# DS130-1_02_G-M.net
KiCad netlist of a schematic drawn in Altium Designer
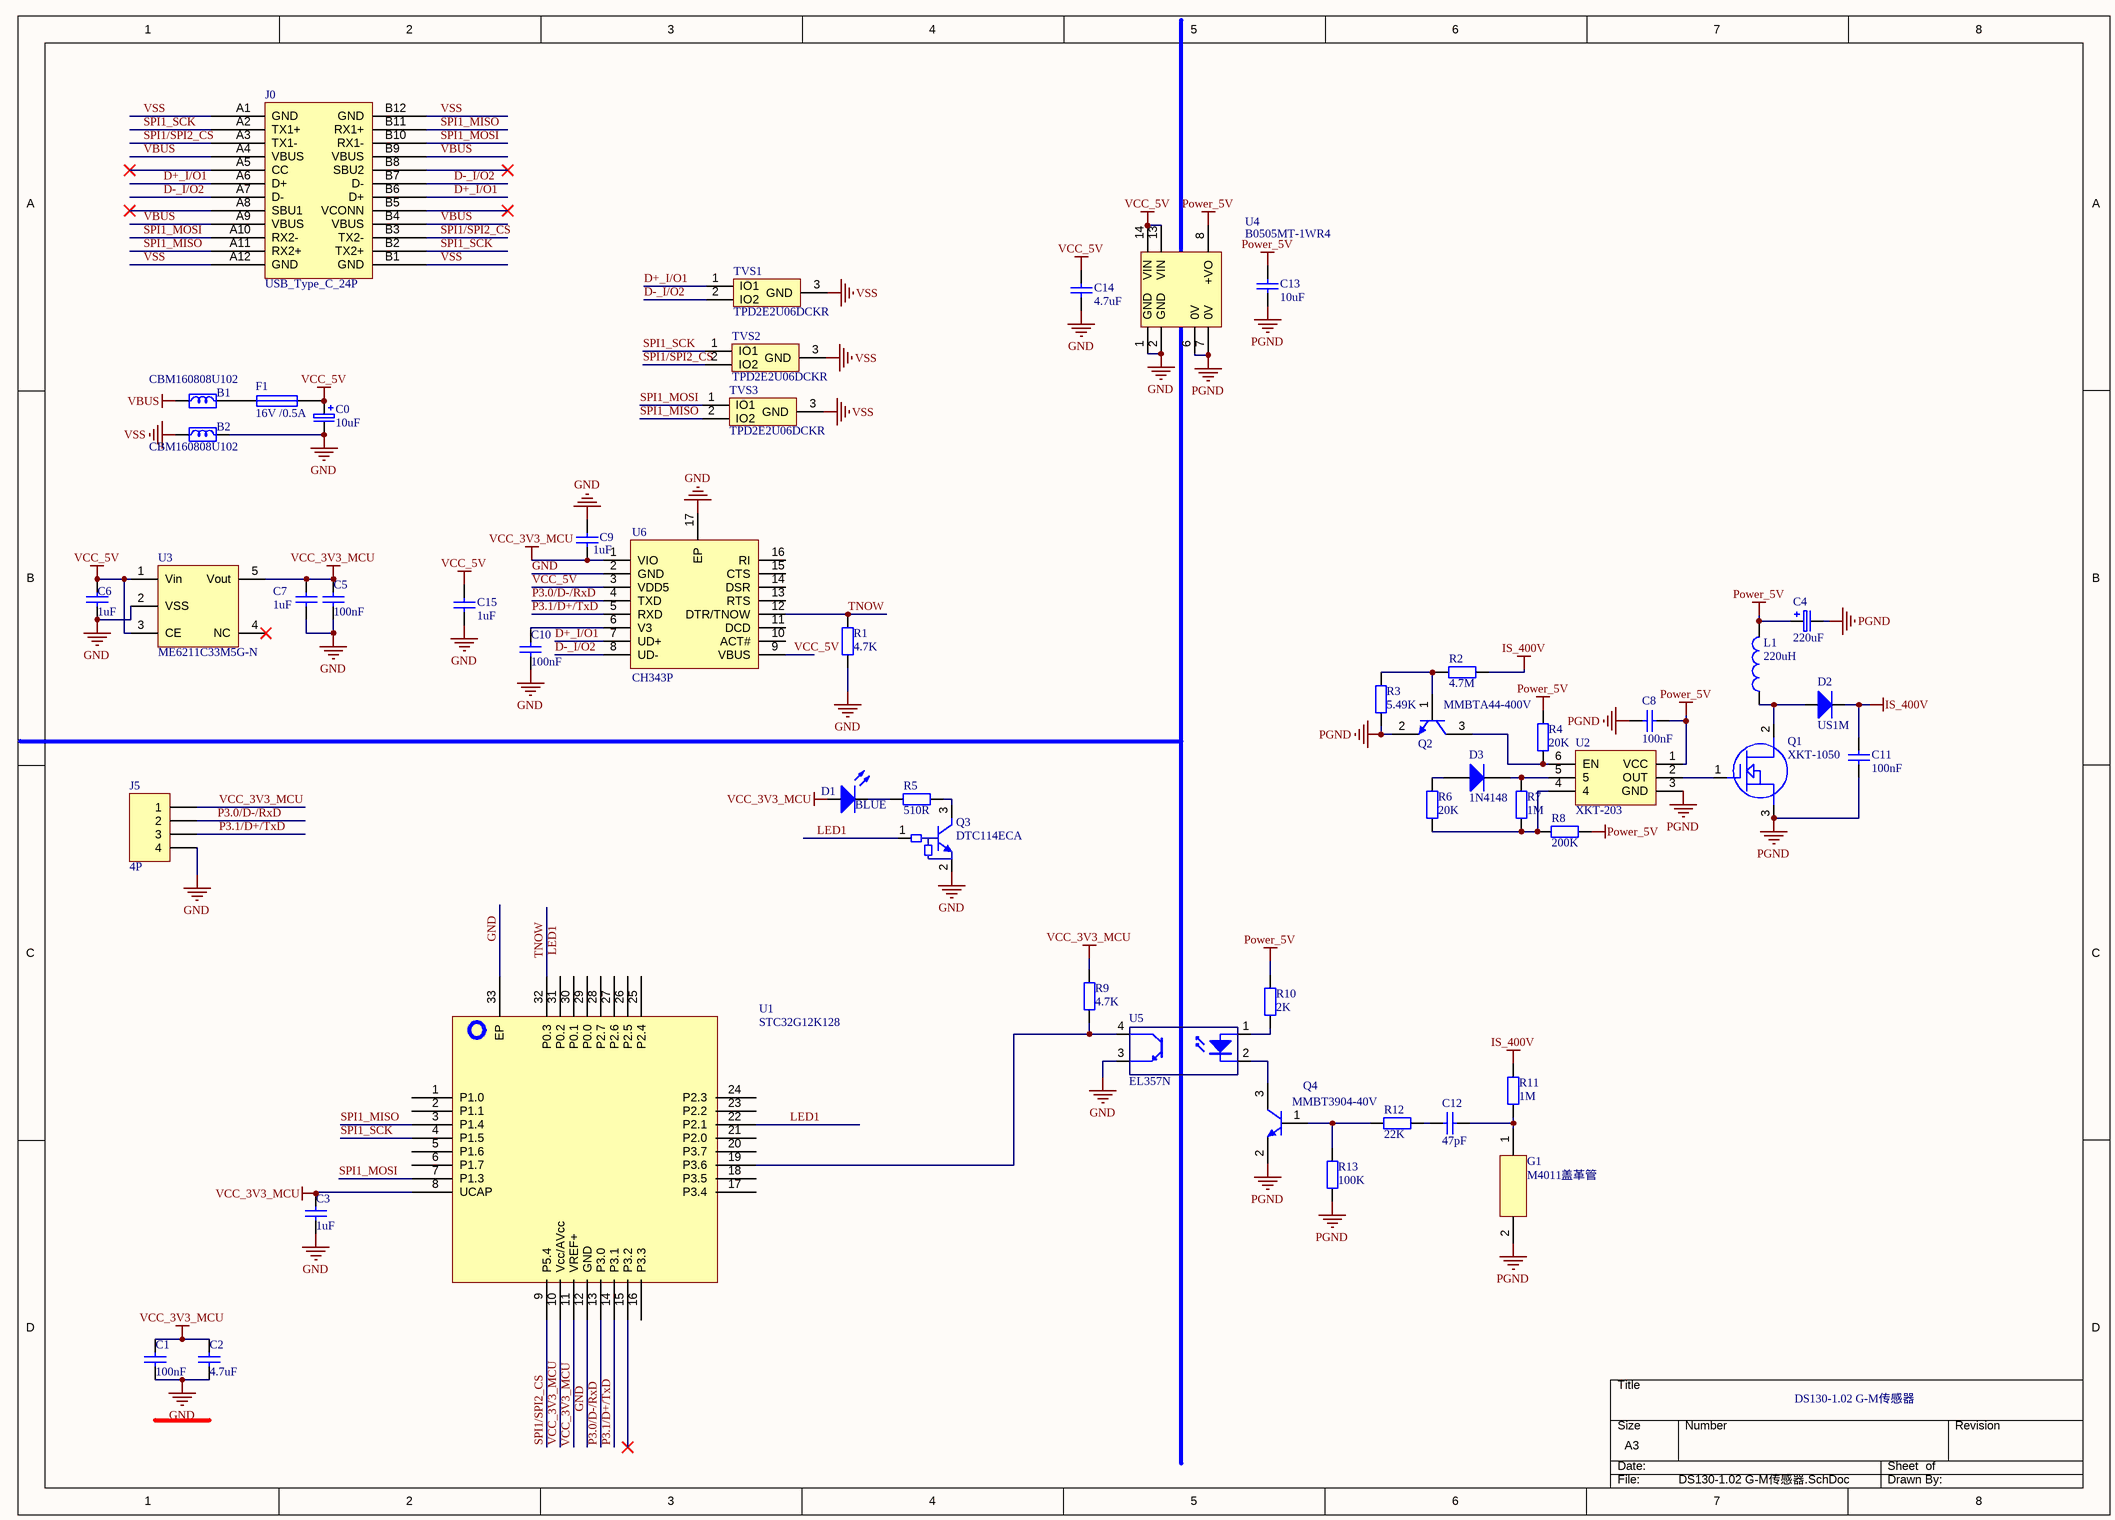
[diagram p0: DS130-1.02 G-M传感器.SchDoc]

(export (version "E")
  (design (tool "Eeschema 10.0.6"))
  (components
    (comp (ref "B1")
      (value "CBM160808U102")
      (footprint "0603Bead")
      (description "贴片磁珠")
      (libsource (lib "AD_SCH") (part "Chip Ferrite Bead 0606"))
    )
    (comp (ref "B2")
      (value "CBM160808U102")
      (footprint "0603Bead")
      (description "贴片磁珠")
      (libsource (lib "AD_SCH") (part "Chip Ferrite Bead 0606"))
    )
    (comp (ref "C0")
      (value "10uF")
      (footprint "AVX_3216-18(1206)_SMD")
      (description "钽电容")
      (fields (field (name "Comment") "AVX_10uF/16V ±10％(C106)"))
      (libsource (lib "AD_SCH") (part "AVX_10uF/16V ±10％(C106)"))
    )
    (comp (ref "C1")
      (value "100nF")
      (footprint "0603CAP")
      (description "贴片电容")
      (fields (field (name "Comment") "SMDCAP00013"))
      (libsource (lib "AD_SCH") (part "MLCC 100nF 50V ±10％ 0603"))
    )
    (comp (ref "C2")
      (value "4.7uF")
      (footprint "0603CAP")
      (description "贴片电容")
      (fields (field (name "Comment") "SMDCAP00012"))
      (libsource (lib "AD_SCH") (part "MLCC 4.7uF 50V ±10％ 0603"))
    )
    (comp (ref "C3")
      (value "1uF")
      (footprint "0603CAP")
      (description "贴片电容")
      (fields (field (name "Comment") "SMDCAP00015"))
      (libsource (lib "AD_SCH") (part "MLCC 1uF 50V ±10％ 0603"))
    )
    (comp (ref "C4")
      (value "220uF")
      (footprint "AVX_7343-31(2917)_SMD")
      (description "钽电容")
      (fields (field (name "Comment") "AVX_220uF/16V ±10％(C227)"))
      (libsource (lib "AD_SCH") (part "AVX_220uF/16V ±10％(C227)"))
    )
    (comp (ref "C5")
      (value "100nF")
      (footprint "0603CAP")
      (description "贴片电容")
      (fields (field (name "Comment") "SMDCAP00013"))
      (libsource (lib "AD_SCH") (part "MLCC 100nF 50V ±10％ 0603"))
    )
    (comp (ref "C6")
      (value "1uF")
      (footprint "0603CAP")
      (description "贴片电容")
      (fields (field (name "Comment") "SMDCAP00015"))
      (libsource (lib "AD_SCH") (part "MLCC 1uF 50V ±10％ 0603"))
    )
    (comp (ref "C7")
      (value "1uF")
      (footprint "0603CAP")
      (description "贴片电容")
      (fields (field (name "Comment") "SMDCAP00015"))
      (libsource (lib "AD_SCH") (part "MLCC 1uF 50V ±10％ 0603"))
    )
    (comp (ref "C8")
      (value "100nF")
      (footprint "0603CAP")
      (description "贴片电容")
      (fields (field (name "Comment") "SMDCAP00013"))
      (libsource (lib "AD_SCH") (part "MLCC 100nF 50V ±10％ 0603"))
    )
    (comp (ref "C9")
      (value "1uF")
      (footprint "0603CAP")
      (description "贴片电容")
      (fields (field (name "Comment") "SMDCAP00015"))
      (libsource (lib "AD_SCH") (part "MLCC 1uF 50V ±10％ 0603"))
    )
    (comp (ref "C10")
      (value "100nF")
      (footprint "0603CAP")
      (description "贴片电容")
      (fields (field (name "Comment") "SMDCAP00013"))
      (libsource (lib "AD_SCH") (part "MLCC 100nF 50V ±10％ 0603"))
    )
    (comp (ref "C11")
      (value "100nF")
      (footprint "DIP_CL_10.16mm")
      (description "插件涤纶电容")
      (fields (field (name "Comment") "DIPCAP03003"))
      (libsource (lib "AD_SCH") (part "CBB22 100nF 630VDC ±5％ DIP2"))
    )
    (comp (ref "C12")
      (value "47pF")
      (footprint "1206CAP")
      (description "贴片电容")
      (fields (field (name "Comment") "MLCC 47pF 1kV ±5％ 1206"))
      (libsource (lib "AD_SCH") (part "MLCC 47pF 1kV ±5％ 1206"))
    )
    (comp (ref "C13")
      (value "10uF")
      (footprint "0603CAP")
      (description "贴片电容")
      (fields (field (name "Comment") "SMDCAP00016"))
      (libsource (lib "AD_SCH") (part "MLCC 10uF 50V ±10％ 0603"))
    )
    (comp (ref "C14")
      (value "4.7uF")
      (footprint "0603CAP")
      (description "贴片电容")
      (fields (field (name "Comment") "SMDCAP00012"))
      (libsource (lib "AD_SCH") (part "MLCC 4.7uF 50V ±10％ 0603"))
    )
    (comp (ref "C15")
      (value "1uF")
      (footprint "0603CAP")
      (description "贴片电容")
      (fields (field (name "Comment") "SMDCAP00015"))
      (libsource (lib "AD_SCH") (part "MLCC 1uF 50V ±10％ 0603"))
    )
    (comp (ref "D1")
      (value "BLUE")
      (footprint "LED_0805")
      (description "贴片LED")
      (fields (field (name "Comment") "SMDLED00010"))
      (libsource (lib "AD_SCH") (part "Chip 蓝色LED 0805"))
    )
    (comp (ref "D2")
      (value "US1M")
      (footprint "SMA/DO-214AC")
      (description "快恢复/高效率二极管")
      (fields (field (name "Comment") "US1M-DO-214AC"))
      (libsource (lib "AD_SCH") (part "US1M-DO-214AC"))
    )
    (comp (ref "D3")
      (value "1N4148")
      (footprint "SOD-123")
      (description "贴片开关二极管 T4")
      (fields (field (name "Comment") "DIPDIODE02001"))
      (libsource (lib "AD_SCH") (part "1N4148W"))
    )
    (comp (ref "F1")
      (value "16V /0.5A")
      (footprint "1206FUSE")
      (description "贴片自恢复保险丝 16V /0.5A")
      (fields (field (name "Comment") "SMD1206-050C-16V"))
      (libsource (lib "AD_SCH") (part "SMD1206-050C-16V"))
    )
    (comp (ref "G1") (value "M4011盖革管") (footprint "M4011-90") (libsource (lib "AD_SCH") (part "M4011盖革管")))
    (comp (ref "J0")
      (value "USB_Type_C_24P")
      (footprint "USB_TYPE_C_24P_Receptacle")
      (libsource (lib "AD_SCH") (part "USB_Type_C_24P"))
    )
    (comp (ref "J5")
      (value "4P")
      (footprint "H4")
      (description "单排直针")
      (fields (field (name "Comment") "DIP4单排直针  间距2mm 针长11mm 铜"))
      (libsource (lib "AD_SCH") (part "DIP4单排直针  间距2mm 针长11mm 铜"))
    )
    (comp (ref "L1")
      (value "220uH")
      (footprint "IND-SMD_L8.0-W8.0")
      (fields (field (name "Comment") "SMD_220uH 8.0*8.0"))
      (libsource (lib "AD_SCH") (part "SMD_220uH 8.0*8.0"))
    )
    (comp (ref "Q1")
      (value "XKT-1050")
      (footprint "TO-252")
      (description "NMOS")
      (libsource (lib "AD_SCH") (part "XKT-1050"))
    )
    (comp (ref "Q2")
      (value "MMBTA44-400V")
      (footprint "SOT23")
      (description "BJT")
      (fields (field (name "Comment") "MMBTA44"))
      (libsource (lib "AD_SCH") (part "MMBTA44"))
    )
    (comp (ref "Q3")
      (value "DTC114ECA")
      (footprint "SOT23")
      (description "数字晶体管")
      (fields (field (name "Comment") "SMDIC000037"))
      (libsource (lib "AD_SCH") (part "DTC114ECA SOT-23 长电"))
    )
    (comp (ref "Q4")
      (value "MMBT3904-40V")
      (footprint "SOT23")
      (description "BJT")
      (fields (field (name "Comment") "MMBT3904"))
      (libsource (lib "AD_SCH") (part "MMBT3904"))
    )
    (comp (ref "R1")
      (value "4.7K")
      (footprint "0603RES")
      (description "贴片电阻")
      (fields (field (name "Comment") "Chip 4.7K 1/16W ±1％ 0603"))
      (libsource (lib "AD_SCH") (part "Chip 4.7K 1/16W ±1％ 0603"))
    )
    (comp (ref "R2")
      (value "4.7M")
      (footprint "1206RES")
      (description "贴片电阻")
      (fields (field (name "Comment") "Chip 4.7M 1/4W ±1％ 1206 500V"))
      (libsource (lib "AD_SCH") (part "Chip 4.7M 1/4W ±1％ 1206 500V"))
    )
    (comp (ref "R3")
      (value "5.49K")
      (footprint "0603RES")
      (description "贴片电阻")
      (fields (field (name "Comment") "Chip 5.49K 1/10W ±1％ 0603"))
      (libsource (lib "AD_SCH") (part "Chip 5.49K 1/10W ±1％ 0603"))
    )
    (comp (ref "R4")
      (value "20K")
      (footprint "0603RES")
      (description "贴片电阻")
      (fields (field (name "Comment") "SMDRES00058"))
      (libsource (lib "AD_SCH") (part "Chip 20K 1/16W ±1％ 0603"))
    )
    (comp (ref "R5")
      (value "510R")
      (footprint "0603RES")
      (description "贴片电阻")
      (fields (field (name "Comment") "SMDRES00030"))
      (libsource (lib "AD_SCH") (part "Chip 510R 1/16W ±1％ 0603"))
    )
    (comp (ref "R6")
      (value "20K")
      (footprint "0603RES")
      (description "贴片电阻")
      (fields (field (name "Comment") "SMDRES00058"))
      (libsource (lib "AD_SCH") (part "Chip 20K 1/16W ±1％ 0603"))
    )
    (comp (ref "R7")
      (value "1M")
      (footprint "0603RES")
      (description "贴片电阻")
      (fields (field (name "Comment") "SMDRES00085"))
      (libsource (lib "AD_SCH") (part "Chip 1M 1/16W ±1％ 0603"))
    )
    (comp (ref "R8")
      (value "200K")
      (footprint "0603RES")
      (description "贴片电阻")
      (fields (field (name "Comment") "SMDRES00075"))
      (libsource (lib "AD_SCH") (part "Chip 200K 1/16W ±1％ 0603"))
    )
    (comp (ref "R9")
      (value "4.7K")
      (footprint "0603RES")
      (description "贴片电阻")
      (fields (field (name "Comment") "Chip 4.7K 1/16W ±1％ 0603"))
      (libsource (lib "AD_SCH") (part "Chip 4.7K 1/16W ±1％ 0603"))
    )
    (comp (ref "R10")
      (value "2K")
      (footprint "0603RES")
      (description "贴片电阻")
      (fields (field (name "Comment") "SMDRES00042"))
      (libsource (lib "AD_SCH") (part "Chip 2K 1/16W ±1％ 0603"))
    )
    (comp (ref "R11")
      (value "1M")
      (footprint "0805RES")
      (description "贴片电阻")
      (fields (field (name "Comment") "Chip 1M 1/10W ±1％ 0805 400V"))
      (libsource (lib "AD_SCH") (part "Chip 1M 1/10W ±1％ 0805 400V"))
    )
    (comp (ref "R12")
      (value "22K")
      (footprint "0603RES")
      (description "贴片电阻")
      (fields (field (name "Comment") "SMDRES00108"))
      (libsource (lib "AD_SCH") (part "Chip 22K 1/16W ±1％ 0603"))
    )
    (comp (ref "R13")
      (value "100K")
      (footprint "0603RES")
      (description "贴片电阻")
      (fields (field (name "Comment") "SMDRES00071"))
      (libsource (lib "AD_SCH") (part "Chip 100K 1/16W ±1％ 0603"))
    )
    (comp (ref "TVS1")
      (value "TPD2E2U06DCKR")
      (footprint "SC-70-3_L2.0-W1.3-P0.65-LS2.1-BL")
      (libsource (lib "AD_SCH") (part "TPD2E2U06DCKR"))
    )
    (comp (ref "TVS2")
      (value "TPD2E2U06DCKR")
      (footprint "SC-70-3_L2.0-W1.3-P0.65-LS2.1-BL")
      (libsource (lib "AD_SCH") (part "TPD2E2U06DCKR"))
    )
    (comp (ref "TVS3")
      (value "TPD2E2U06DCKR")
      (footprint "SC-70-3_L2.0-W1.3-P0.65-LS2.1-BL")
      (libsource (lib "AD_SCH") (part "TPD2E2U06DCKR"))
    )
    (comp (ref "U1")
      (value "STC32G12K128")
      (footprint "QFN-32-L4.0-W4.0")
      (description "单片机芯片")
      (fields (field (name "Comment") "STC32G12K128_35I QFN32"))
      (libsource (lib "AD_SCH") (part "STC32G12K128_35I QFN32"))
    )
    (comp (ref "U2") (value "XKT-203") (footprint "SOT23-6") (libsource (lib "AD_SCH") (part "XKT-203")))
    (comp (ref "U3")
      (value "ME6211C33M5G-N")
      (footprint "SOT23-5")
      (description "稳压芯片")
      (libsource (lib "AD_SCH") (part "ME6211C33M5G-N"))
    )
    (comp (ref "U4")
      (value "B0505MT-1WR4")
      (footprint "DFN-14_7P_L9.0-W7.0-P1.27-BL_B0505MT-1WR4")
      (libsource (lib "AD_SCH") (part "B0505MT-1WR4"))
    )
    (comp (ref "U5")
      (value "EL357N")
      (footprint "SO-4")
      (description "光耦")
      (libsource (lib "AD_SCH") (part "EL357N"))
    )
    (comp (ref "U6") (value "CH343P") (footprint "QFN-16_L3_W3") (libsource (lib "AD_SCH") (part "CH343P")))
  )
  (nets
    (net (code "1") (name "/D+_I{slash}O1") (class "Default")
      (node (ref "J0") (pin "A6") (pinfunction "D+_A6") (pintype "passive"))
      (node (ref "J0") (pin "B6") (pinfunction "D+_B6") (pintype "passive"))
      (node (ref "TVS1") (pin "1") (pinfunction "IO1_1") (pintype "passive"))
      (node (ref "U6") (pin "7") (pinfunction "UD+_7") (pintype "passive"))
    )
    (net (code "2") (name "/D-_I{slash}O2") (class "Default")
      (node (ref "J0") (pin "A7") (pinfunction "D-_A7") (pintype "passive"))
      (node (ref "J0") (pin "B7") (pinfunction "D-_B7") (pintype "passive"))
      (node (ref "TVS1") (pin "2") (pinfunction "IO2_2") (pintype "passive"))
      (node (ref "U6") (pin "8") (pinfunction "UD-_8") (pintype "passive"))
    )
    (net (code "3") (name "/LED1") (class "Default")
      (node (ref "Q3") (pin "1") (pinfunction "IN_1") (pintype "passive"))
      (node (ref "U1") (pin "22") (pinfunction "P2.1_22") (pintype "passive"))
    )
    (net (code "4") (name "/P3.0{slash}D-{slash}RxD") (class "Default")
      (node (ref "J5") (pin "2") (pinfunction "2_2") (pintype "passive"))
      (node (ref "U1") (pin "13") (pinfunction "P3.0_13") (pintype "passive"))
      (node (ref "U6") (pin "4") (pinfunction "TXD_4") (pintype "passive"))
    )
    (net (code "5") (name "/P3.1{slash}D+{slash}TxD") (class "Default")
      (node (ref "J5") (pin "3") (pinfunction "3_3") (pintype "passive"))
      (node (ref "U1") (pin "14") (pinfunction "P3.1_14") (pintype "passive"))
      (node (ref "U6") (pin "5") (pinfunction "RXD_5") (pintype "passive"))
    )
    (net (code "6") (name "/SPI1_MISO") (class "Default")
      (node (ref "J0") (pin "A11") (pinfunction "RX2+_A11") (pintype "passive"))
      (node (ref "J0") (pin "B11") (pinfunction "RX1+_B11") (pintype "passive"))
      (node (ref "TVS3") (pin "2") (pinfunction "IO2_2") (pintype "passive"))
      (node (ref "U1") (pin "3") (pinfunction "P1.4_3") (pintype "passive"))
    )
    (net (code "7") (name "/SPI1_MOSI") (class "Default")
      (node (ref "J0") (pin "A10") (pinfunction "RX2-_A10") (pintype "passive"))
      (node (ref "J0") (pin "B10") (pinfunction "RX1-_B10") (pintype "passive"))
      (node (ref "TVS3") (pin "1") (pinfunction "IO1_1") (pintype "passive"))
      (node (ref "U1") (pin "7") (pinfunction "P1.3_7") (pintype "passive"))
    )
    (net (code "8") (name "/SPI1_SCK") (class "Default")
      (node (ref "J0") (pin "A2") (pinfunction "TX1+_A2") (pintype "passive"))
      (node (ref "J0") (pin "B2") (pinfunction "TX2+_B2") (pintype "passive"))
      (node (ref "TVS2") (pin "1") (pinfunction "IO1_1") (pintype "passive"))
      (node (ref "U1") (pin "4") (pinfunction "P1.5_4") (pintype "passive"))
    )
    (net (code "9") (name "/SPI1{slash}SPI2_CS") (class "Default")
      (node (ref "J0") (pin "A3") (pinfunction "TX1-_A3") (pintype "passive"))
      (node (ref "J0") (pin "B3") (pinfunction "TX2-_B3") (pintype "passive"))
      (node (ref "TVS2") (pin "2") (pinfunction "IO2_2") (pintype "passive"))
      (node (ref "U1") (pin "9") (pinfunction "P5.4_9") (pintype "passive"))
    )
    (net (code "10") (name "/TNOW") (class "Default")
      (node (ref "R1") (pin "2") (pinfunction "2_2") (pintype "passive"))
      (node (ref "U1") (pin "32") (pinfunction "P0.3_32") (pintype "passive"))
      (node (ref "U6") (pin "12") (pinfunction "DTR/TNOW_12") (pintype "passive"))
    )
    (net (code "11") (name "GND") (class "Default")
      (node (ref "B2") (pin "2") (pinfunction "2_2") (pintype "passive"))
      (node (ref "C0") (pin "2") (pinfunction "2_2") (pintype "passive"))
      (node (ref "C1") (pin "1") (pinfunction "1_1") (pintype "passive"))
      (node (ref "C10") (pin "1") (pinfunction "1_1") (pintype "passive"))
      (node (ref "C14") (pin "1") (pinfunction "1_1") (pintype "passive"))
      (node (ref "C15") (pin "1") (pinfunction "1_1") (pintype "passive"))
      (node (ref "C2") (pin "1") (pinfunction "1_1") (pintype "passive"))
      (node (ref "C3") (pin "1") (pinfunction "1_1") (pintype "passive"))
      (node (ref "C5") (pin "1") (pinfunction "1_1") (pintype "passive"))
      (node (ref "C6") (pin "1") (pinfunction "1_1") (pintype "passive"))
      (node (ref "C7") (pin "1") (pinfunction "1_1") (pintype "passive"))
      (node (ref "C9") (pin "2") (pinfunction "2_2") (pintype "passive"))
      (node (ref "J5") (pin "4") (pinfunction "4_4") (pintype "passive"))
      (node (ref "Q3") (pin "2") (pinfunction "GND_2") (pintype "passive"))
      (node (ref "R1") (pin "1") (pinfunction "1_1") (pintype "passive"))
      (node (ref "U1") (pin "12") (pinfunction "GND_12") (pintype "passive"))
      (node (ref "U1") (pin "33") (pinfunction "EP_33") (pintype "passive"))
      (node (ref "U3") (pin "2") (pinfunction "VSS_2") (pintype "passive"))
      (node (ref "U4") (pin "1") (pinfunction "GND_1") (pintype "passive"))
      (node (ref "U4") (pin "2") (pinfunction "GND_2") (pintype "passive"))
      (node (ref "U5") (pin "3") (pinfunction "E_3") (pintype "passive"))
      (node (ref "U6") (pin "17") (pinfunction "EP_17") (pintype "passive"))
      (node (ref "U6") (pin "2") (pinfunction "GND_2") (pintype "passive"))
    )
    (net (code "12") (name "IS_400V") (class "Default")
      (node (ref "C11") (pin "1") (pinfunction "1_1") (pintype "passive"))
      (node (ref "D2") (pin "2") (pinfunction "K_2") (pintype "passive"))
      (node (ref "R11") (pin "2") (pinfunction "2_2") (pintype "passive"))
      (node (ref "R2") (pin "2") (pinfunction "2_2") (pintype "passive"))
    )
    (net (code "13") (name "Net-(B1-Pad2)") (class "Default")
      (node (ref "B1") (pin "2") (pinfunction "2_2") (pintype "passive"))
      (node (ref "F1") (pin "1") (pinfunction "1_1") (pintype "passive"))
    )
    (net (code "14") (name "Net-(C12-Pad1)") (class "Default")
      (node (ref "C12") (pin "1") (pinfunction "1_1") (pintype "passive"))
      (node (ref "G1") (pin "1") (pinfunction "1_1") (pintype "passive"))
      (node (ref "R11") (pin "1") (pinfunction "1_1") (pintype "passive"))
    )
    (net (code "15") (name "Net-(C12-Pad2)") (class "Default")
      (node (ref "C12") (pin "2") (pinfunction "2_2") (pintype "passive"))
      (node (ref "R12") (pin "1") (pinfunction "1_1") (pintype "passive"))
    )
    (net (code "16") (name "Net-(D1-K)") (class "Default")
      (node (ref "D1") (pin "2") (pinfunction "K_2") (pintype "passive"))
      (node (ref "R5") (pin "1") (pinfunction "1_1") (pintype "passive"))
    )
    (net (code "17") (name "Net-(D2-A)") (class "Default")
      (node (ref "D2") (pin "1") (pinfunction "A_1") (pintype "passive"))
      (node (ref "L1") (pin "1") (pinfunction "1_1") (pintype "passive"))
      (node (ref "Q1") (pin "2") (pinfunction "D_2") (pintype "passive"))
    )
    (net (code "18") (name "Net-(D3-A)") (class "Default")
      (node (ref "D3") (pin "1") (pinfunction "A_1") (pintype "passive"))
      (node (ref "R6") (pin "2") (pinfunction "2_2") (pintype "passive"))
    )
    (net (code "19") (name "Net-(D3-K)") (class "Default")
      (node (ref "D3") (pin "2") (pinfunction "K_2") (pintype "passive"))
      (node (ref "R7") (pin "2") (pinfunction "2_2") (pintype "passive"))
      (node (ref "U2") (pin "5") (pinfunction "5_5") (pintype "passive"))
    )
    (net (code "20") (name "Net-(Q1-G)") (class "Default")
      (node (ref "Q1") (pin "1") (pinfunction "G_1") (pintype "passive"))
      (node (ref "U2") (pin "2") (pinfunction "OUT_2") (pintype "passive"))
    )
    (net (code "21") (name "Net-(Q2-B)") (class "Default")
      (node (ref "Q2") (pin "1") (pinfunction "B_1") (pintype "passive"))
      (node (ref "R2") (pin "1") (pinfunction "1_1") (pintype "passive"))
      (node (ref "R3") (pin "2") (pinfunction "2_2") (pintype "passive"))
    )
    (net (code "22") (name "Net-(Q2-C)") (class "Default")
      (node (ref "Q2") (pin "3") (pinfunction "C_3") (pintype "passive"))
      (node (ref "R4") (pin "1") (pinfunction "1_1") (pintype "passive"))
      (node (ref "U2") (pin "6") (pinfunction "EN_6") (pintype "passive"))
    )
    (net (code "23") (name "Net-(Q3-OUT)") (class "Default")
      (node (ref "Q3") (pin "3") (pinfunction "OUT_3") (pintype "passive"))
      (node (ref "R5") (pin "2") (pinfunction "2_2") (pintype "passive"))
    )
    (net (code "24") (name "Net-(Q4-B)") (class "Default")
      (node (ref "Q4") (pin "1") (pinfunction "B_1") (pintype "passive"))
      (node (ref "R12") (pin "2") (pinfunction "2_2") (pintype "passive"))
      (node (ref "R13") (pin "2") (pinfunction "2_2") (pintype "passive"))
    )
    (net (code "25") (name "Net-(Q4-C)") (class "Default")
      (node (ref "Q4") (pin "3") (pinfunction "C_3") (pintype "passive"))
      (node (ref "U5") (pin "2") (pinfunction "K_2") (pintype "passive"))
    )
    (net (code "26") (name "Net-(R6-Pad1)") (class "Default")
      (node (ref "R6") (pin "1") (pinfunction "1_1") (pintype "passive"))
      (node (ref "R7") (pin "1") (pinfunction "1_1") (pintype "passive"))
      (node (ref "R8") (pin "2") (pinfunction "2_2") (pintype "passive"))
      (node (ref "U2") (pin "4") (pinfunction "4_4") (pintype "passive"))
    )
    (net (code "27") (name "Net-(U1-P3.6)") (class "Default")
      (node (ref "R9") (pin "1") (pinfunction "1_1") (pintype "passive"))
      (node (ref "U1") (pin "19") (pinfunction "P3.6_19") (pintype "passive"))
      (node (ref "U5") (pin "4") (pinfunction "C_4") (pintype "passive"))
    )
    (net (code "28") (name "Net-(U5-A)") (class "Default")
      (node (ref "R10") (pin "2") (pinfunction "2_2") (pintype "passive"))
      (node (ref "U5") (pin "1") (pinfunction "A_1") (pintype "passive"))
    )
    (net (code "29") (name "Net-(U6-V3)") (class "Default")
      (node (ref "C10") (pin "2") (pinfunction "2_2") (pintype "passive"))
      (node (ref "U6") (pin "6") (pinfunction "V3_6") (pintype "passive"))
    )
    (net (code "30") (name "PGND") (class "Default")
      (node (ref "C11") (pin "2") (pinfunction "2_2") (pintype "passive"))
      (node (ref "C13") (pin "1") (pinfunction "1_1") (pintype "passive"))
      (node (ref "C4") (pin "2") (pinfunction "2_2") (pintype "passive"))
      (node (ref "C8") (pin "1") (pinfunction "1_1") (pintype "passive"))
      (node (ref "G1") (pin "2") (pinfunction "2_2") (pintype "passive"))
      (node (ref "Q1") (pin "3") (pinfunction "S_3") (pintype "passive"))
      (node (ref "Q2") (pin "2") (pinfunction "E_2") (pintype "passive"))
      (node (ref "Q4") (pin "2") (pinfunction "E_2") (pintype "passive"))
      (node (ref "R13") (pin "1") (pinfunction "1_1") (pintype "passive"))
      (node (ref "R3") (pin "1") (pinfunction "1_1") (pintype "passive"))
      (node (ref "U2") (pin "3") (pinfunction "GND_3") (pintype "passive"))
      (node (ref "U4") (pin "6") (pinfunction "0V_6") (pintype "passive"))
      (node (ref "U4") (pin "7") (pinfunction "0V_7") (pintype "passive"))
    )
    (net (code "31") (name "Power_5V") (class "Default")
      (node (ref "C13") (pin "2") (pinfunction "2_2") (pintype "passive"))
      (node (ref "C4") (pin "1") (pinfunction "1_1") (pintype "passive"))
      (node (ref "C8") (pin "2") (pinfunction "2_2") (pintype "passive"))
      (node (ref "L1") (pin "2") (pinfunction "2_2") (pintype "passive"))
      (node (ref "R10") (pin "1") (pinfunction "1_1") (pintype "passive"))
      (node (ref "R4") (pin "2") (pinfunction "2_2") (pintype "passive"))
      (node (ref "R8") (pin "1") (pinfunction "1_1") (pintype "passive"))
      (node (ref "U2") (pin "1") (pinfunction "VCC_1") (pintype "passive"))
      (node (ref "U4") (pin "8") (pinfunction "+VO_8") (pintype "passive"))
    )
    (net (code "32") (name "VBUS") (class "Default")
      (node (ref "B1") (pin "1") (pinfunction "1_1") (pintype "passive"))
      (node (ref "J0") (pin "A4") (pinfunction "VBUS_A4") (pintype "passive"))
      (node (ref "J0") (pin "A9") (pinfunction "VBUS_A9") (pintype "passive"))
      (node (ref "J0") (pin "B4") (pinfunction "VBUS_B4") (pintype "passive"))
      (node (ref "J0") (pin "B9") (pinfunction "VBUS_B9") (pintype "passive"))
    )
    (net (code "33") (name "VCC_3V3_MCU") (class "Default")
      (node (ref "C1") (pin "2") (pinfunction "2_2") (pintype "passive"))
      (node (ref "C2") (pin "2") (pinfunction "2_2") (pintype "passive"))
      (node (ref "C3") (pin "2") (pinfunction "2_2") (pintype "passive"))
      (node (ref "C5") (pin "2") (pinfunction "2_2") (pintype "passive"))
      (node (ref "C7") (pin "2") (pinfunction "2_2") (pintype "passive"))
      (node (ref "C9") (pin "1") (pinfunction "1_1") (pintype "passive"))
      (node (ref "D1") (pin "1") (pinfunction "A_1") (pintype "passive"))
      (node (ref "J5") (pin "1") (pinfunction "1_1") (pintype "passive"))
      (node (ref "R9") (pin "2") (pinfunction "2_2") (pintype "passive"))
      (node (ref "U1") (pin "10") (pinfunction "Vcc/AVcc_10") (pintype "passive"))
      (node (ref "U1") (pin "11") (pinfunction "VREF+_11") (pintype "passive"))
      (node (ref "U1") (pin "8") (pinfunction "UCAP_8") (pintype "passive"))
      (node (ref "U3") (pin "5") (pinfunction "Vout_5") (pintype "passive"))
      (node (ref "U6") (pin "1") (pinfunction "VIO_1") (pintype "passive"))
    )
    (net (code "34") (name "VCC_5V") (class "Default")
      (node (ref "C0") (pin "1") (pinfunction "1_1") (pintype "passive"))
      (node (ref "C14") (pin "2") (pinfunction "2_2") (pintype "passive"))
      (node (ref "C15") (pin "2") (pinfunction "2_2") (pintype "passive"))
      (node (ref "C6") (pin "2") (pinfunction "2_2") (pintype "passive"))
      (node (ref "F1") (pin "2") (pinfunction "2_2") (pintype "passive"))
      (node (ref "U3") (pin "1") (pinfunction "Vin_1") (pintype "passive"))
      (node (ref "U3") (pin "3") (pinfunction "CE_3") (pintype "passive"))
      (node (ref "U4") (pin "13") (pinfunction "VIN_13") (pintype "passive"))
      (node (ref "U4") (pin "14") (pinfunction "VIN_14") (pintype "passive"))
      (node (ref "U6") (pin "3") (pinfunction "VDD5_3") (pintype "passive"))
      (node (ref "U6") (pin "9") (pinfunction "VBUS_9") (pintype "passive"))
    )
    (net (code "35") (name "VSS") (class "Default")
      (node (ref "B2") (pin "1") (pinfunction "1_1") (pintype "passive"))
      (node (ref "J0") (pin "A1") (pinfunction "GND_A1") (pintype "passive"))
      (node (ref "J0") (pin "A12") (pinfunction "GND_A12") (pintype "passive"))
      (node (ref "J0") (pin "B1") (pinfunction "GND_B1") (pintype "passive"))
      (node (ref "J0") (pin "B12") (pinfunction "GND_B12") (pintype "passive"))
      (node (ref "TVS1") (pin "3") (pinfunction "GND_3") (pintype "passive"))
      (node (ref "TVS2") (pin "3") (pinfunction "GND_3") (pintype "passive"))
      (node (ref "TVS3") (pin "3") (pinfunction "GND_3") (pintype "passive"))
    )
    (net (code "36") (name "unconnected-(J0-CC-PadA5)") (class "Default")
      (node (ref "J0") (pin "A5") (pinfunction "CC_A5") (pintype "passive+no_connect"))
    )
    (net (code "37") (name "unconnected-(J0-SBU1-PadA8)") (class "Default")
      (node (ref "J0") (pin "A8") (pinfunction "SBU1_A8") (pintype "passive+no_connect"))
    )
    (net (code "38") (name "unconnected-(J0-SBU2-PadB8)") (class "Default")
      (node (ref "J0") (pin "B8") (pinfunction "SBU2_B8") (pintype "passive+no_connect"))
    )
    (net (code "39") (name "unconnected-(J0-VCONN-PadB5)") (class "Default")
      (node (ref "J0") (pin "B5") (pinfunction "VCONN_B5") (pintype "passive+no_connect"))
    )
    (net (code "40") (name "unconnected-(U1-P0.0-Pad29)") (class "Default")
      (node (ref "U1") (pin "29") (pinfunction "P0.0_29") (pintype "passive"))
    )
    (net (code "41") (name "unconnected-(U1-P0.1-Pad30)") (class "Default")
      (node (ref "U1") (pin "30") (pinfunction "P0.1_30") (pintype "passive"))
    )
    (net (code "42") (name "unconnected-(U1-P0.2-Pad31)") (class "Default")
      (node (ref "U1") (pin "31") (pinfunction "P0.2_31") (pintype "passive"))
    )
    (net (code "43") (name "unconnected-(U1-P1.0-Pad1)") (class "Default")
      (node (ref "U1") (pin "1") (pinfunction "P1.0_1") (pintype "passive"))
    )
    (net (code "44") (name "unconnected-(U1-P1.1-Pad2)") (class "Default")
      (node (ref "U1") (pin "2") (pinfunction "P1.1_2") (pintype "passive"))
    )
    (net (code "45") (name "unconnected-(U1-P1.6-Pad5)") (class "Default")
      (node (ref "U1") (pin "5") (pinfunction "P1.6_5") (pintype "passive"))
    )
    (net (code "46") (name "unconnected-(U1-P1.7-Pad6)") (class "Default")
      (node (ref "U1") (pin "6") (pinfunction "P1.7_6") (pintype "passive"))
    )
    (net (code "47") (name "unconnected-(U1-P2.0-Pad21)") (class "Default")
      (node (ref "U1") (pin "21") (pinfunction "P2.0_21") (pintype "passive"))
    )
    (net (code "48") (name "unconnected-(U1-P2.2-Pad23)") (class "Default")
      (node (ref "U1") (pin "23") (pinfunction "P2.2_23") (pintype "passive"))
    )
    (net (code "49") (name "unconnected-(U1-P2.3-Pad24)") (class "Default")
      (node (ref "U1") (pin "24") (pinfunction "P2.3_24") (pintype "passive"))
    )
    (net (code "50") (name "unconnected-(U1-P2.4-Pad25)") (class "Default")
      (node (ref "U1") (pin "25") (pinfunction "P2.4_25") (pintype "passive"))
    )
    (net (code "51") (name "unconnected-(U1-P2.5-Pad26)") (class "Default")
      (node (ref "U1") (pin "26") (pinfunction "P2.5_26") (pintype "passive"))
    )
    (net (code "52") (name "unconnected-(U1-P2.6-Pad27)") (class "Default")
      (node (ref "U1") (pin "27") (pinfunction "P2.6_27") (pintype "passive"))
    )
    (net (code "53") (name "unconnected-(U1-P2.7-Pad28)") (class "Default")
      (node (ref "U1") (pin "28") (pinfunction "P2.7_28") (pintype "passive"))
    )
    (net (code "54") (name "unconnected-(U1-P3.2-Pad15)") (class "Default")
      (node (ref "U1") (pin "15") (pinfunction "P3.2_15") (pintype "passive+no_connect"))
    )
    (net (code "55") (name "unconnected-(U1-P3.3-Pad16)") (class "Default")
      (node (ref "U1") (pin "16") (pinfunction "P3.3_16") (pintype "passive"))
    )
    (net (code "56") (name "unconnected-(U1-P3.4-Pad17)") (class "Default")
      (node (ref "U1") (pin "17") (pinfunction "P3.4_17") (pintype "passive"))
    )
    (net (code "57") (name "unconnected-(U1-P3.5-Pad18)") (class "Default")
      (node (ref "U1") (pin "18") (pinfunction "P3.5_18") (pintype "passive"))
    )
    (net (code "58") (name "unconnected-(U1-P3.7-Pad20)") (class "Default")
      (node (ref "U1") (pin "20") (pinfunction "P3.7_20") (pintype "passive"))
    )
    (net (code "59") (name "unconnected-(U3-NC-Pad4)") (class "Default")
      (node (ref "U3") (pin "4") (pinfunction "NC_4") (pintype "passive+no_connect"))
    )
    (net (code "60") (name "unconnected-(U6-ACT#-Pad10)") (class "Default")
      (node (ref "U6") (pin "10") (pinfunction "ACT#_10") (pintype "passive"))
    )
    (net (code "61") (name "unconnected-(U6-CTS-Pad15)") (class "Default")
      (node (ref "U6") (pin "15") (pinfunction "CTS_15") (pintype "passive"))
    )
    (net (code "62") (name "unconnected-(U6-DCD-Pad11)") (class "Default")
      (node (ref "U6") (pin "11") (pinfunction "DCD_11") (pintype "passive"))
    )
    (net (code "63") (name "unconnected-(U6-DSR-Pad14)") (class "Default")
      (node (ref "U6") (pin "14") (pinfunction "DSR_14") (pintype "passive"))
    )
    (net (code "64") (name "unconnected-(U6-RI-Pad16)") (class "Default")
      (node (ref "U6") (pin "16") (pinfunction "RI_16") (pintype "passive"))
    )
    (net (code "65") (name "unconnected-(U6-RTS-Pad13)") (class "Default")
      (node (ref "U6") (pin "13") (pinfunction "RTS_13") (pintype "passive"))
    )
  )
)
